# Rocketometer2148_MPU6050.net
KiCad netlist of a schematic drawn in EAGLE
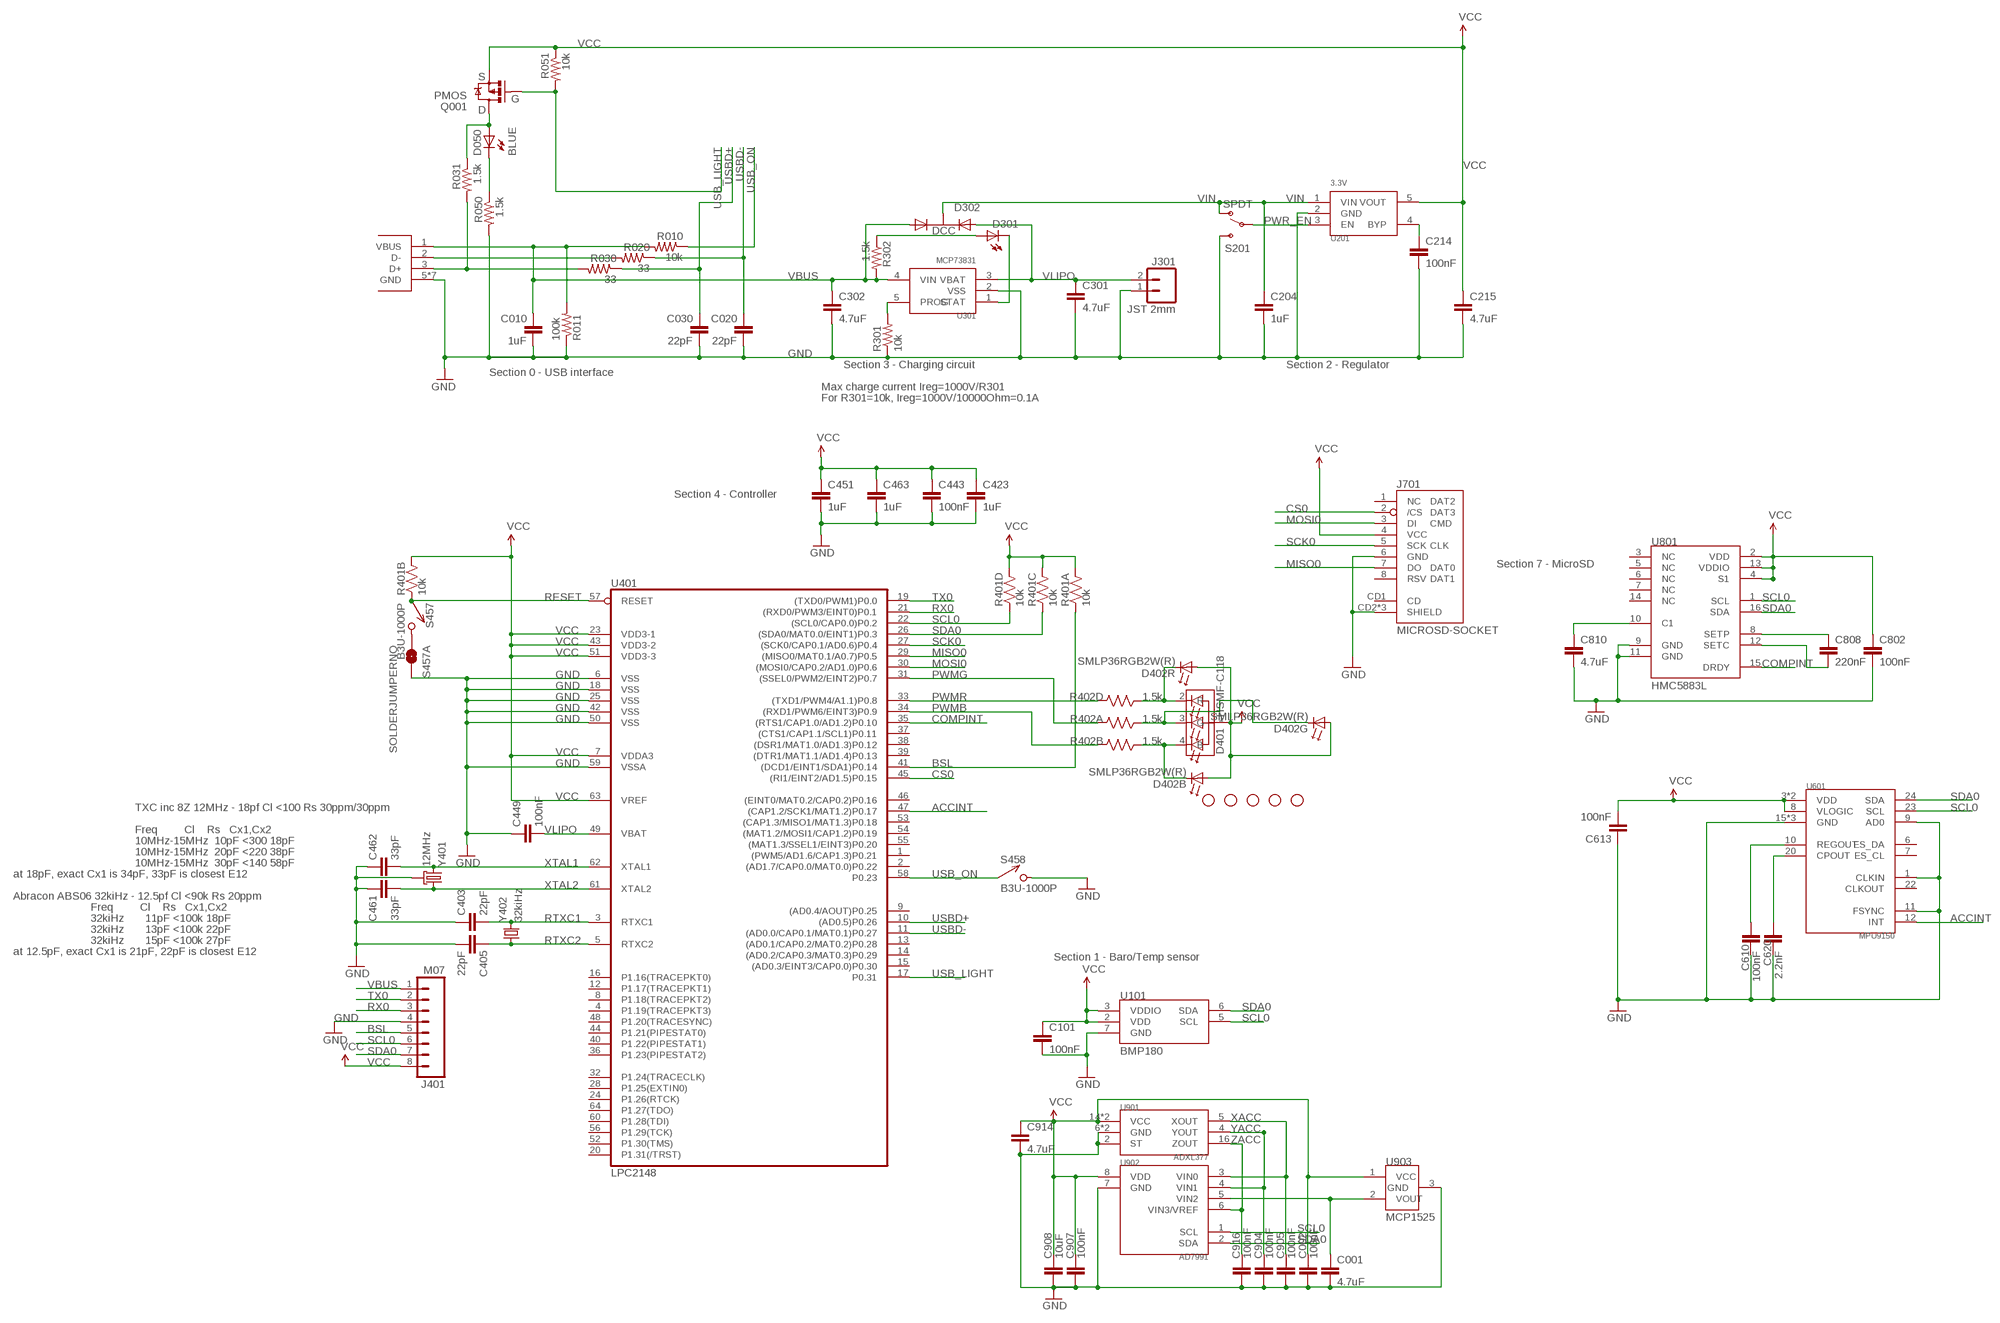
[diagram p0: schematic, sheet 1]

(export (version "E")
  (design (tool "Eeschema 10.0.6"))
  (components
    (comp (ref "C001")
      (value "4.7uF")
      (footprint "eagle-import:0402-CAP")
      (libsource (lib "eagle-import") (part "CAP0402-CAP"))
    )
    (comp (ref "C002")
      (value "100nF")
      (footprint "eagle-import:0402-CAP")
      (libsource (lib "eagle-import") (part "SparkFun-Passives_CAP0402-CAP"))
    )
    (comp (ref "C010")
      (value "1uF")
      (footprint "eagle-import:0402-CAP")
      (libsource (lib "eagle-import") (part "CAP0402-CAP"))
    )
    (comp (ref "C020")
      (value "22pF")
      (footprint "eagle-import:0402-CAP")
      (libsource (lib "eagle-import") (part "CAP0402-CAP"))
    )
    (comp (ref "C030")
      (value "22pF")
      (footprint "eagle-import:0402-CAP")
      (libsource (lib "eagle-import") (part "CAP0402-CAP"))
    )
    (comp (ref "C101")
      (value "100nF")
      (footprint "eagle-import:0402-CAP")
      (libsource (lib "eagle-import") (part "CAP0402-CAP"))
    )
    (comp (ref "C204")
      (value "1uF")
      (footprint "eagle-import:0402-CAP")
      (libsource (lib "eagle-import") (part "CAP0402-CAP"))
    )
    (comp (ref "C214")
      (value "100nF")
      (footprint "eagle-import:0402-CAP")
      (libsource (lib "eagle-import") (part "CAP0402-CAP"))
    )
    (comp (ref "C215")
      (value "4.7uF")
      (footprint "eagle-import:0402-CAP")
      (libsource (lib "eagle-import") (part "CAP0402-CAP"))
    )
    (comp (ref "C301")
      (value "4.7uF")
      (footprint "eagle-import:0402-CAP")
      (libsource (lib "eagle-import") (part "CAP0402-CAP"))
    )
    (comp (ref "C302")
      (value "4.7uF")
      (footprint "eagle-import:0402-CAP")
      (libsource (lib "eagle-import") (part "CAP0402-CAP"))
    )
    (comp (ref "C403")
      (value "22pF")
      (footprint "eagle-import:0402-CAP")
      (libsource (lib "eagle-import") (part "CAP0402-CAP"))
    )
    (comp (ref "C405")
      (value "22pF")
      (footprint "eagle-import:0402-CAP")
      (libsource (lib "eagle-import") (part "CAP0402-CAP"))
    )
    (comp (ref "C423")
      (value "1uF")
      (footprint "eagle-import:0402-CAP")
      (libsource (lib "eagle-import") (part "CAP0402-CAP"))
    )
    (comp (ref "C443")
      (value "100nF")
      (footprint "eagle-import:0402-CAP")
      (libsource (lib "eagle-import") (part "CAP0402-CAP"))
    )
    (comp (ref "C449")
      (value "100nF")
      (footprint "eagle-import:0402-CAP")
      (libsource (lib "eagle-import") (part "CAP0402-CAP"))
    )
    (comp (ref "C451")
      (value "1uF")
      (footprint "eagle-import:0402-CAP")
      (libsource (lib "eagle-import") (part "CAP0402-CAP"))
    )
    (comp (ref "C461")
      (value "33pF")
      (footprint "eagle-import:0402-CAP")
      (libsource (lib "eagle-import") (part "CAP0402-CAP"))
    )
    (comp (ref "C462")
      (value "33pF")
      (footprint "eagle-import:0402-CAP")
      (libsource (lib "eagle-import") (part "CAP0402-CAP"))
    )
    (comp (ref "C463")
      (value "1uF")
      (footprint "eagle-import:0402-CAP")
      (libsource (lib "eagle-import") (part "CAP0402-CAP"))
    )
    (comp (ref "C610")
      (value "100nF")
      (footprint "eagle-import:0402-CAP")
      (libsource (lib "eagle-import") (part "CAP0402-CAP"))
    )
    (comp (ref "C613")
      (value "100nF")
      (footprint "eagle-import:0402-CAP")
      (libsource (lib "eagle-import") (part "CAP0402-CAP"))
    )
    (comp (ref "C620")
      (value "2.2nF")
      (footprint "eagle-import:0402-CAP")
      (libsource (lib "eagle-import") (part "CAP0402-CAP"))
    )
    (comp (ref "C802")
      (value "100nF")
      (footprint "eagle-import:0402-CAP")
      (libsource (lib "eagle-import") (part "CAP0402-CAP"))
    )
    (comp (ref "C808")
      (value "220nF")
      (footprint "eagle-import:0402-CAP")
      (libsource (lib "eagle-import") (part "CAP0402-CAP"))
    )
    (comp (ref "C810")
      (value "4.7uF")
      (footprint "eagle-import:0402-CAP")
      (libsource (lib "eagle-import") (part "CAP0402-CAP"))
    )
    (comp (ref "C904")
      (value "100nF")
      (footprint "eagle-import:0402-CAP")
      (libsource (lib "eagle-import") (part "CAP0402-CAP"))
    )
    (comp (ref "C905")
      (value "100nF")
      (footprint "eagle-import:0402-CAP")
      (libsource (lib "eagle-import") (part "CAP0402-CAP"))
    )
    (comp (ref "C907")
      (value "100nF")
      (footprint "eagle-import:0402-CAP")
      (libsource (lib "eagle-import") (part "SparkFun-Passives_CAP0402-CAP"))
    )
    (comp (ref "C908")
      (value "10uF")
      (footprint "eagle-import:0603-CAP")
      (libsource (lib "eagle-import") (part "CAP0603-CAP"))
    )
    (comp (ref "C914")
      (value "4.7uF")
      (footprint "eagle-import:0402-CAP")
      (libsource (lib "eagle-import") (part "CAP0402-CAP"))
    )
    (comp (ref "C916")
      (value "100nF")
      (footprint "eagle-import:0402-CAP")
      (libsource (lib "eagle-import") (part "CAP0402-CAP"))
    )
    (comp (ref "D050")
      (value "BLUE")
      (footprint "eagle-import:LED-0603")
      (libsource (lib "eagle-import") (part "LED0603"))
    )
    (comp (ref "D301")
      (value "YELLOW")
      (footprint "eagle-import:LED-0603")
      (libsource (lib "eagle-import") (part "LED0603"))
    )
    (comp (ref "D302")
      (value "DCC")
      (footprint "eagle-import:SOT-23-3")
      (libsource (lib "eagle-import") (part "PMEG2005CT"))
    )
    (comp (ref "D401")
      (value "HSMF-C118")
      (footprint "eagle-import:HSMF-C118")
      (libsource (lib "eagle-import") (part "HSMF-C118"))
    )
    (comp (ref "D402")
      (value "SMLP36RGB2W(R)")
      (footprint "eagle-import:SMLP36")
      (libsource (lib "eagle-import") (part "SMLP36RGB2W(R)"))
    )
    (comp (ref "J001")
      (value "USB_MICROB_JST")
      (footprint "eagle-import:UB-MC5BR3-SD204-4S")
      (libsource (lib "eagle-import") (part "USB_MICROB_JST"))
    )
    (comp (ref "J301")
      (value "JST 2mm")
      (footprint "eagle-import:JST-2-SMD")
      (libsource (lib "eagle-import") (part "M02-JST-2MM-SMT"))
    )
    (comp (ref "J401")
      (value "M07")
      (footprint "eagle-import:1X08")
      (libsource (lib "eagle-import") (part "M081X08"))
    )
    (comp (ref "J701")
      (value "MICROSD-SOCKET")
      (footprint "eagle-import:MICROSD-SOCKET-PP")
      (libsource (lib "eagle-import") (part "MICROSD-SOCKET"))
    )
    (comp (ref "JP1")
      (value "STAND-OFFTIGHT")
      (footprint "eagle-import:STAND-OFF-TIGHT")
      (libsource (lib "eagle-import") (part "STAND-OFFTIGHT"))
    )
    (comp (ref "JP2")
      (value "STAND-OFFTIGHT")
      (footprint "eagle-import:STAND-OFF-TIGHT")
      (libsource (lib "eagle-import") (part "STAND-OFFTIGHT"))
    )
    (comp (ref "JP3")
      (value "STAND-OFFTIGHT")
      (footprint "eagle-import:STAND-OFF-TIGHT")
      (libsource (lib "eagle-import") (part "STAND-OFFTIGHT"))
    )
    (comp (ref "JP4")
      (value "STAND-OFFTIGHT")
      (footprint "eagle-import:STAND-OFF-TIGHT")
      (libsource (lib "eagle-import") (part "STAND-OFFTIGHT"))
    )
    (comp (ref "JP5")
      (value "STAND-OFFTIGHT")
      (footprint "eagle-import:STAND-OFF-TIGHT")
      (libsource (lib "eagle-import") (part "STAND-OFFTIGHT"))
    )
    (comp (ref "Q001")
      (value "PMOS")
      (footprint "eagle-import:SOT23-3")
      (libsource (lib "eagle-import") (part "MOSFET-PCHANNELSMD"))
    )
    (comp (ref "R010")
      (value "10k")
      (footprint "eagle-import:0402-RES")
      (libsource (lib "eagle-import") (part "RESISTOR0402-RES"))
    )
    (comp (ref "R011")
      (value "100k")
      (footprint "eagle-import:0402-RES")
      (libsource (lib "eagle-import") (part "RESISTOR0402-RES"))
    )
    (comp (ref "R020")
      (value "33")
      (footprint "eagle-import:0402-RES")
      (libsource (lib "eagle-import") (part "RESISTOR0402-RES"))
    )
    (comp (ref "R030")
      (value "33")
      (footprint "eagle-import:0402-RES")
      (libsource (lib "eagle-import") (part "RESISTOR0402-RES"))
    )
    (comp (ref "R031")
      (value "1.5k")
      (footprint "eagle-import:0402-RES")
      (libsource (lib "eagle-import") (part "RESISTOR0402-RES"))
    )
    (comp (ref "R050")
      (value "1.5k")
      (footprint "eagle-import:0402-RES")
      (libsource (lib "eagle-import") (part "RESISTOR0402-RES"))
    )
    (comp (ref "R051")
      (value "10k")
      (footprint "eagle-import:0402-RES")
      (libsource (lib "eagle-import") (part "RESISTOR0402-RES"))
    )
    (comp (ref "R301")
      (value "10k")
      (footprint "eagle-import:0402-RES")
      (libsource (lib "eagle-import") (part "RESISTOR0402-RES"))
    )
    (comp (ref "R302")
      (value "1.5k")
      (footprint "eagle-import:0402-RES")
      (libsource (lib "eagle-import") (part "RESISTOR0402-RES"))
    )
    (comp (ref "R401")
      (value "10k")
      (footprint "eagle-import:CRA04")
      (fields (field (name "DIGIKEY") "CRA4S810KCT-ND"))
      (libsource (lib "eagle-import") (part "RP404"))
    )
    (comp (ref "R402")
      (value "1.5k")
      (footprint "eagle-import:CRA04")
      (fields (field (name "DIGIKEY") "CRA4S81.5KCT-ND"))
      (libsource (lib "eagle-import") (part "RP404"))
    )
    (comp (ref "S201")
      (value "SPDT")
      (footprint "eagle-import:AYZ0202")
      (libsource (lib "eagle-import") (part "SWITCH-SPSTSMD"))
    )
    (comp (ref "S457")
      (value "B3U-1000P")
      (footprint "eagle-import:B3U-1000P")
      (libsource (lib "eagle-import") (part "B3U-1000P"))
    )
    (comp (ref "S457A")
      (value "SOLDERJUMPERNO")
      (footprint "eagle-import:SJ_2S-NO")
      (libsource (lib "eagle-import") (part "SOLDERJUMPERNO"))
    )
    (comp (ref "S458")
      (value "B3U-1000P")
      (footprint "eagle-import:B3U-1000P")
      (libsource (lib "eagle-import") (part "B3U-1000P"))
    )
    (comp (ref "U101")
      (value "BMP180")
      (footprint "eagle-import:BMP180")
      (libsource (lib "eagle-import") (part "BMP180"))
    )
    (comp (ref "U201")
      (value "3.3V")
      (footprint "eagle-import:SOT-23-5")
      (libsource (lib "eagle-import") (part "MIC5319D5"))
    )
    (comp (ref "U301")
      (value "MCP73831")
      (footprint "eagle-import:SOT-23-5")
      (libsource (lib "eagle-import") (part "MCP73831"))
    )
    (comp (ref "U401")
      (value "LPC2148")
      (footprint "eagle-import:SQFP-S-10X10-64")
      (libsource (lib "eagle-import") (part "LPC213X"))
    )
    (comp (ref "U601")
      (value "MPU9150")
      (footprint "eagle-import:LLGA24")
      (libsource (lib "eagle-import") (part "MPU9150"))
    )
    (comp (ref "U801")
      (value "HMC5883L")
      (footprint "eagle-import:16LPCC")
      (libsource (lib "eagle-import") (part "HMC5883LSMD"))
    )
    (comp (ref "U901")
      (value "ADXL377")
      (footprint "eagle-import:ADXL377")
      (libsource (lib "eagle-import") (part "ADXL377"))
    )
    (comp (ref "U902")
      (value "AD7991")
      (footprint "eagle-import:SOT-23-8")
      (libsource (lib "eagle-import") (part "AD799X"))
    )
    (comp (ref "U903")
      (value "MCP1525")
      (footprint "eagle-import:SOT-23-3")
      (libsource (lib "eagle-import") (part "MCP1525"))
    )
    (comp (ref "Y401")
      (value "12MHz")
      (footprint "eagle-import:CRYSTAL_SMD_2MM_2_5MM")
      (libsource (lib "eagle-import") (part "CX2520"))
    )
    (comp (ref "Y402")
      (value "32kiHz")
      (footprint "eagle-import:ABS06")
      (libsource (lib "eagle-import") (part "ABS06"))
    )
  )
  (nets
    (net (code "1") (name "/ACCINT") (class "Default")
      (node (ref "U401") (pin "47") (pinfunction "(CAP1.2/SCK1/MAT1.2)P0.17_47") (pintype "bidirectional"))
      (node (ref "U601") (pin "12") (pinfunction "INT_12") (pintype "bidirectional"))
    )
    (net (code "2") (name "/BSL") (class "Default")
      (node (ref "J401") (pin "5") (pinfunction "5_5") (pintype "passive"))
      (node (ref "R401") (pin "1") (pinfunction "1_1") (pintype "passive"))
      (node (ref "U401") (pin "41") (pinfunction "(DCD1/EINT1/SDA1)P0.14_41") (pintype "bidirectional"))
    )
    (net (code "3") (name "/COMPINT") (class "Default")
      (node (ref "U401") (pin "35") (pinfunction "(RTS1/CAP1.0/AD1.2)P0.10_35") (pintype "bidirectional"))
      (node (ref "U801") (pin "15") (pinfunction "DRDY_15") (pintype "bidirectional"))
    )
    (net (code "4") (name "/CS0") (class "Default")
      (node (ref "J701") (pin "2") (pinfunction "/CS_2") (pintype "bidirectional"))
      (node (ref "U401") (pin "45") (pinfunction "(RI1/EINT2/AD1.5)P0.15_45") (pintype "bidirectional"))
    )
    (net (code "5") (name "/MISO0") (class "Default")
      (node (ref "J701") (pin "7") (pinfunction "DO_7") (pintype "bidirectional"))
      (node (ref "U401") (pin "29") (pinfunction "(MISO0/MAT0.1/A0.7)P0.5_29") (pintype "bidirectional"))
    )
    (net (code "6") (name "/MOSI0") (class "Default")
      (node (ref "J701") (pin "3") (pinfunction "DI_3") (pintype "bidirectional"))
      (node (ref "U401") (pin "30") (pinfunction "(MOSI0/CAP0.2/AD1.0)P0.6_30") (pintype "bidirectional"))
    )
    (net (code "7") (name "/PWMB") (class "Default")
      (node (ref "R402") (pin "7") (pinfunction "2_7") (pintype "passive"))
      (node (ref "U401") (pin "34") (pinfunction "(RXD1/PWM6/EINT3)P0.9_34") (pintype "bidirectional"))
    )
    (net (code "8") (name "/PWMG") (class "Default")
      (node (ref "R402") (pin "8") (pinfunction "2_8") (pintype "passive"))
      (node (ref "U401") (pin "31") (pinfunction "(SSEL0/PWM2/EINT2)P0.7_31") (pintype "bidirectional"))
    )
    (net (code "9") (name "/PWMR") (class "Default")
      (node (ref "R402") (pin "5") (pinfunction "2_5") (pintype "passive"))
      (node (ref "U401") (pin "33") (pinfunction "(TXD1/PWM4/A1.1)P0.8_33") (pintype "bidirectional"))
    )
    (net (code "10") (name "/PWR_EN") (class "Default")
      (node (ref "S201") (pin "2") (pinfunction "P_2") (pintype "passive"))
      (node (ref "U201") (pin "3") (pinfunction "EN_3") (pintype "bidirectional"))
    )
    (net (code "11") (name "/RESET") (class "Default")
      (node (ref "R401") (pin "2") (pinfunction "1_2") (pintype "passive"))
      (node (ref "S457") (pin "P$1") (pinfunction "1_P$1") (pintype "bidirectional"))
      (node (ref "U401") (pin "57") (pinfunction "RESET_57") (pintype "input"))
    )
    (net (code "12") (name "/RTXC1") (class "Default")
      (node (ref "C403") (pin "2") (pinfunction "2_2") (pintype "passive"))
      (node (ref "U401") (pin "3") (pinfunction "RTXC1_3") (pintype "input"))
      (node (ref "Y402") (pin "2") (pinfunction "2_2") (pintype "passive"))
    )
    (net (code "13") (name "/RTXC2") (class "Default")
      (node (ref "C405") (pin "1") (pinfunction "1_1") (pintype "passive"))
      (node (ref "U401") (pin "5") (pinfunction "RTXC2_5") (pintype "output"))
      (node (ref "Y402") (pin "1") (pinfunction "1_1") (pintype "passive"))
    )
    (net (code "14") (name "/RX0") (class "Default")
      (node (ref "J401") (pin "3") (pinfunction "3_3") (pintype "passive"))
      (node (ref "U401") (pin "21") (pinfunction "(RXD0/PWM3/EINT0)P0.1_21") (pintype "bidirectional"))
    )
    (net (code "15") (name "/SCK0") (class "Default")
      (node (ref "J701") (pin "5") (pinfunction "SCK_5") (pintype "bidirectional"))
      (node (ref "U401") (pin "27") (pinfunction "(SCK0/CAP0.1/AD0.6)P0.4_27") (pintype "bidirectional"))
    )
    (net (code "16") (name "/SCL0") (class "Default")
      (node (ref "J401") (pin "6") (pinfunction "6_6") (pintype "passive"))
      (node (ref "R401") (pin "4") (pinfunction "1_4") (pintype "passive"))
      (node (ref "U101") (pin "5") (pinfunction "SCL_5") (pintype "input"))
      (node (ref "U401") (pin "22") (pinfunction "(SCL0/CAP0.0)P0.2_22") (pintype "bidirectional"))
      (node (ref "U601") (pin "23") (pinfunction "SCL_23") (pintype "bidirectional"))
      (node (ref "U801") (pin "1") (pinfunction "SCL_1") (pintype "bidirectional"))
      (node (ref "U902") (pin "1") (pinfunction "SCL_1") (pintype "bidirectional"))
    )
    (net (code "17") (name "/SDA0") (class "Default")
      (node (ref "J401") (pin "7") (pinfunction "7_7") (pintype "passive"))
      (node (ref "R401") (pin "3") (pinfunction "1_3") (pintype "passive"))
      (node (ref "U101") (pin "6") (pinfunction "SDA_6") (pintype "bidirectional"))
      (node (ref "U401") (pin "26") (pinfunction "(SDA0/MAT0.0/EINT1)P0.3_26") (pintype "bidirectional"))
      (node (ref "U601") (pin "24") (pinfunction "SDA_24") (pintype "bidirectional"))
      (node (ref "U801") (pin "16") (pinfunction "SDA_16") (pintype "bidirectional"))
      (node (ref "U902") (pin "2") (pinfunction "SDA_2") (pintype "bidirectional"))
    )
    (net (code "18") (name "/TX0") (class "Default")
      (node (ref "J401") (pin "2") (pinfunction "2_2") (pintype "passive"))
      (node (ref "U401") (pin "19") (pinfunction "(TXD0/PWM1)P0.0_19") (pintype "bidirectional"))
    )
    (net (code "19") (name "/USBD+") (class "Default")
      (node (ref "C030") (pin "1") (pinfunction "1_1") (pintype "passive"))
      (node (ref "R030") (pin "1") (pinfunction "1_1") (pintype "passive"))
      (node (ref "U401") (pin "10") (pinfunction "(AD0.5)P0.26_10") (pintype "bidirectional"))
    )
    (net (code "20") (name "/USBD-") (class "Default")
      (node (ref "C020") (pin "1") (pinfunction "1_1") (pintype "passive"))
      (node (ref "R020") (pin "1") (pinfunction "1_1") (pintype "passive"))
      (node (ref "U401") (pin "11") (pinfunction "(AD0.0/CAP0.1/MAT0.1)P0.27_11") (pintype "bidirectional"))
    )
    (net (code "21") (name "/USB_LIGHT") (class "Default")
      (node (ref "Q001") (pin "1") (pinfunction "G_1") (pintype "passive"))
      (node (ref "R051") (pin "2") (pinfunction "2_2") (pintype "passive"))
      (node (ref "U401") (pin "17") (pinfunction "P0.31_17") (pintype "output"))
    )
    (net (code "22") (name "/USB_ON") (class "Default")
      (node (ref "R010") (pin "1") (pinfunction "1_1") (pintype "passive"))
      (node (ref "S458") (pin "P$1") (pinfunction "1_P$1") (pintype "bidirectional"))
      (node (ref "U401") (pin "58") (pinfunction "P0.23_58") (pintype "bidirectional"))
    )
    (net (code "23") (name "/VBUS") (class "Default")
      (node (ref "C010") (pin "1") (pinfunction "1_1") (pintype "passive"))
      (node (ref "C302") (pin "1") (pinfunction "1_1") (pintype "passive"))
      (node (ref "D302") (pin "1") (pinfunction "A1_1") (pintype "passive"))
      (node (ref "J001") (pin "1") (pinfunction "VBUS_1") (pintype "bidirectional"))
      (node (ref "J401") (pin "1") (pinfunction "1_1") (pintype "passive"))
      (node (ref "R010") (pin "2") (pinfunction "2_2") (pintype "passive"))
      (node (ref "R011") (pin "2") (pinfunction "2_2") (pintype "passive"))
      (node (ref "R302") (pin "2") (pinfunction "2_2") (pintype "passive"))
      (node (ref "U301") (pin "4") (pinfunction "VIN_4") (pintype "power_in"))
    )
    (net (code "24") (name "/VIN") (class "Default")
      (node (ref "C204") (pin "1") (pinfunction "1_1") (pintype "passive"))
      (node (ref "D302") (pin "3") (pinfunction "K_3") (pintype "passive"))
      (node (ref "S201") (pin "1") (pinfunction "O_1") (pintype "passive"))
      (node (ref "U201") (pin "1") (pinfunction "VIN_1") (pintype "bidirectional"))
    )
    (net (code "25") (name "/VLIPO") (class "Default")
      (node (ref "C301") (pin "1") (pinfunction "1_1") (pintype "passive"))
      (node (ref "C449") (pin "2") (pinfunction "2_2") (pintype "passive"))
      (node (ref "D302") (pin "2") (pinfunction "A2_2") (pintype "passive"))
      (node (ref "J301") (pin "2") (pinfunction "2_2") (pintype "passive"))
      (node (ref "U301") (pin "3") (pinfunction "VBAT_3") (pintype "power_in"))
      (node (ref "U401") (pin "49") (pinfunction "VBAT_49") (pintype "power_in"))
    )
    (net (code "26") (name "/XACC") (class "Default")
      (node (ref "C905") (pin "1") (pinfunction "1_1") (pintype "passive"))
      (node (ref "U901") (pin "5") (pinfunction "XOUT_5") (pintype "bidirectional"))
      (node (ref "U902") (pin "3") (pinfunction "VIN0_3") (pintype "bidirectional"))
    )
    (net (code "27") (name "/XTAL1") (class "Default")
      (node (ref "C462") (pin "2") (pinfunction "2_2") (pintype "passive"))
      (node (ref "U401") (pin "62") (pinfunction "XTAL1_62") (pintype "input"))
      (node (ref "Y401") (pin "3") (pinfunction "2_3") (pintype "passive"))
    )
    (net (code "28") (name "/XTAL2") (class "Default")
      (node (ref "C461") (pin "2") (pinfunction "2_2") (pintype "passive"))
      (node (ref "U401") (pin "61") (pinfunction "XTAL2_61") (pintype "output"))
      (node (ref "Y401") (pin "1") (pinfunction "1_1") (pintype "passive"))
    )
    (net (code "29") (name "/YACC") (class "Default")
      (node (ref "C904") (pin "1") (pinfunction "1_1") (pintype "passive"))
      (node (ref "U901") (pin "4") (pinfunction "YOUT_4") (pintype "bidirectional"))
      (node (ref "U902") (pin "4") (pinfunction "VIN1_4") (pintype "bidirectional"))
    )
    (net (code "30") (name "/ZACC") (class "Default")
      (node (ref "C916") (pin "1") (pinfunction "1_1") (pintype "passive"))
      (node (ref "U901") (pin "16") (pinfunction "ZOUT_16") (pintype "bidirectional"))
      (node (ref "U902") (pin "6") (pinfunction "VIN3/VREF_6") (pintype "bidirectional"))
    )
    (net (code "31") (name "GND") (class "Default")
      (node (ref "C001") (pin "2") (pinfunction "2_2") (pintype "passive"))
      (node (ref "C002") (pin "2") (pinfunction "2_2") (pintype "passive"))
      (node (ref "C010") (pin "2") (pinfunction "2_2") (pintype "passive"))
      (node (ref "C020") (pin "2") (pinfunction "2_2") (pintype "passive"))
      (node (ref "C030") (pin "2") (pinfunction "2_2") (pintype "passive"))
      (node (ref "C101") (pin "2") (pinfunction "2_2") (pintype "passive"))
      (node (ref "C204") (pin "2") (pinfunction "2_2") (pintype "passive"))
      (node (ref "C214") (pin "2") (pinfunction "2_2") (pintype "passive"))
      (node (ref "C215") (pin "2") (pinfunction "2_2") (pintype "passive"))
      (node (ref "C301") (pin "2") (pinfunction "2_2") (pintype "passive"))
      (node (ref "C302") (pin "2") (pinfunction "2_2") (pintype "passive"))
      (node (ref "C403") (pin "1") (pinfunction "1_1") (pintype "passive"))
      (node (ref "C405") (pin "2") (pinfunction "2_2") (pintype "passive"))
      (node (ref "C423") (pin "2") (pinfunction "2_2") (pintype "passive"))
      (node (ref "C443") (pin "2") (pinfunction "2_2") (pintype "passive"))
      (node (ref "C449") (pin "1") (pinfunction "1_1") (pintype "passive"))
      (node (ref "C451") (pin "2") (pinfunction "2_2") (pintype "passive"))
      (node (ref "C461") (pin "1") (pinfunction "1_1") (pintype "passive"))
      (node (ref "C462") (pin "1") (pinfunction "1_1") (pintype "passive"))
      (node (ref "C463") (pin "2") (pinfunction "2_2") (pintype "passive"))
      (node (ref "C610") (pin "2") (pinfunction "2_2") (pintype "passive"))
      (node (ref "C613") (pin "1") (pinfunction "1_1") (pintype "passive"))
      (node (ref "C620") (pin "1") (pinfunction "1_1") (pintype "passive"))
      (node (ref "C802") (pin "2") (pinfunction "2_2") (pintype "passive"))
      (node (ref "C810") (pin "2") (pinfunction "2_2") (pintype "passive"))
      (node (ref "C904") (pin "2") (pinfunction "2_2") (pintype "passive"))
      (node (ref "C905") (pin "2") (pinfunction "2_2") (pintype "passive"))
      (node (ref "C907") (pin "2") (pinfunction "2_2") (pintype "passive"))
      (node (ref "C908") (pin "2") (pinfunction "2_2") (pintype "passive"))
      (node (ref "C914") (pin "2") (pinfunction "2_2") (pintype "passive"))
      (node (ref "C916") (pin "2") (pinfunction "2_2") (pintype "passive"))
      (node (ref "J001") (pin "5") (pinfunction "GND_5") (pintype "bidirectional"))
      (node (ref "J001") (pin "P$10") (pinfunction "GND_P$10") (pintype "bidirectional"))
      (node (ref "J001") (pin "P$11") (pinfunction "GND_P$11") (pintype "bidirectional"))
      (node (ref "J001") (pin "P$6") (pinfunction "GND_P$6") (pintype "bidirectional"))
      (node (ref "J001") (pin "P$7") (pinfunction "GND_P$7") (pintype "bidirectional"))
      (node (ref "J001") (pin "P$8") (pinfunction "GND_P$8") (pintype "bidirectional"))
      (node (ref "J001") (pin "P$9") (pinfunction "GND_P$9") (pintype "bidirectional"))
      (node (ref "J301") (pin "1") (pinfunction "1_1") (pintype "passive"))
      (node (ref "J401") (pin "4") (pinfunction "4_4") (pintype "passive"))
      (node (ref "J701") (pin "6") (pinfunction "GND_6") (pintype "bidirectional"))
      (node (ref "J701") (pin "CD2") (pinfunction "SHIELD_CD2") (pintype "bidirectional"))
      (node (ref "J701") (pin "GND1") (pinfunction "SHIELD_GND1") (pintype "bidirectional"))
      (node (ref "J701") (pin "GND3") (pinfunction "SHIELD_GND3") (pintype "bidirectional"))
      (node (ref "R011") (pin "1") (pinfunction "1_1") (pintype "passive"))
      (node (ref "R050") (pin "2") (pinfunction "2_2") (pintype "passive"))
      (node (ref "R301") (pin "1") (pinfunction "1_1") (pintype "passive"))
      (node (ref "S201") (pin "3") (pinfunction "S_3") (pintype "passive"))
      (node (ref "S457A") (pin "2") (pinfunction "2_2") (pintype "passive"))
      (node (ref "S458") (pin "P$2") (pinfunction "2_P$2") (pintype "bidirectional"))
      (node (ref "U101") (pin "7") (pinfunction "GND_7") (pintype "power_in"))
      (node (ref "U201") (pin "2") (pinfunction "GND_2") (pintype "bidirectional"))
      (node (ref "U301") (pin "2") (pinfunction "VSS_2") (pintype "power_in"))
      (node (ref "U401") (pin "18") (pinfunction "VSS_18") (pintype "power_in"))
      (node (ref "U401") (pin "25") (pinfunction "VSS_25") (pintype "power_in"))
      (node (ref "U401") (pin "42") (pinfunction "VSS_42") (pintype "power_in"))
      (node (ref "U401") (pin "50") (pinfunction "VSS_50") (pintype "power_in"))
      (node (ref "U401") (pin "59") (pinfunction "VSSA_59") (pintype "power_in"))
      (node (ref "U401") (pin "6") (pinfunction "VSS_6") (pintype "power_in"))
      (node (ref "U601") (pin "1") (pinfunction "CLKIN_1") (pintype "bidirectional"))
      (node (ref "U601") (pin "11") (pinfunction "FSYNC_11") (pintype "bidirectional"))
      (node (ref "U601") (pin "15") (pinfunction "GND_15") (pintype "bidirectional"))
      (node (ref "U601") (pin "17") (pinfunction "GND_17") (pintype "bidirectional"))
      (node (ref "U601") (pin "18") (pinfunction "GND_18") (pintype "bidirectional"))
      (node (ref "U601") (pin "9") (pinfunction "AD0_9") (pintype "bidirectional"))
      (node (ref "U801") (pin "11") (pinfunction "GND_11") (pintype "bidirectional"))
      (node (ref "U801") (pin "9") (pinfunction "GND_9") (pintype "bidirectional"))
      (node (ref "U901") (pin "2") (pinfunction "ST_2") (pintype "bidirectional"))
      (node (ref "U901") (pin "6") (pinfunction "GND_6") (pintype "bidirectional"))
      (node (ref "U901") (pin "7") (pinfunction "GND_7") (pintype "bidirectional"))
      (node (ref "U902") (pin "7") (pinfunction "GND_7") (pintype "bidirectional"))
      (node (ref "U903") (pin "3") (pinfunction "GND_3") (pintype "bidirectional"))
      (node (ref "Y401") (pin "2") (pinfunction "GND_2") (pintype "passive"))
      (node (ref "Y401") (pin "4") (pinfunction "GND_4") (pintype "passive"))
    )
    (net (code "32") (name "Net-(D050-PadC)") (class "Default")
      (node (ref "D050") (pin "C") (pinfunction "C_C") (pintype "passive"))
      (node (ref "R050") (pin "1") (pinfunction "1_1") (pintype "passive"))
    )
    (net (code "33") (name "Net-(D301-PadA)") (class "Default")
      (node (ref "D301") (pin "A") (pinfunction "A_A") (pintype "passive"))
      (node (ref "R302") (pin "1") (pinfunction "1_1") (pintype "passive"))
    )
    (net (code "34") (name "Net-(D401-B)") (class "Default")
      (node (ref "D401") (pin "4") (pinfunction "B_4") (pintype "passive"))
      (node (ref "D402") (pin "1") (pinfunction "C_1") (pintype "passive"))
      (node (ref "R402") (pin "2") (pinfunction "1_2") (pintype "passive"))
    )
    (net (code "35") (name "Net-(D401-G)") (class "Default")
      (node (ref "D401") (pin "3") (pinfunction "G_3") (pintype "passive"))
      (node (ref "D402") (pin "5") (pinfunction "C_5") (pintype "passive"))
      (node (ref "R402") (pin "1") (pinfunction "1_1") (pintype "passive"))
    )
    (net (code "36") (name "Net-(D401-R)") (class "Default")
      (node (ref "D401") (pin "2") (pinfunction "R_2") (pintype "passive"))
      (node (ref "D402") (pin "3") (pinfunction "C_3") (pintype "passive"))
      (node (ref "R402") (pin "4") (pinfunction "1_4") (pintype "passive"))
    )
    (net (code "37") (name "Net-(J001-D+)") (class "Default")
      (node (ref "J001") (pin "3") (pinfunction "D+_3") (pintype "bidirectional"))
      (node (ref "R030") (pin "2") (pinfunction "2_2") (pintype "passive"))
      (node (ref "R031") (pin "2") (pinfunction "2_2") (pintype "passive"))
    )
    (net (code "38") (name "Net-(J001-D-)") (class "Default")
      (node (ref "J001") (pin "2") (pinfunction "D-_2") (pintype "bidirectional"))
      (node (ref "R020") (pin "2") (pinfunction "2_2") (pintype "passive"))
    )
    (net (code "39") (name "Net-(Q001-D)") (class "Default")
      (node (ref "D050") (pin "A") (pinfunction "A_A") (pintype "passive"))
      (node (ref "Q001") (pin "3") (pinfunction "D_3") (pintype "passive"))
      (node (ref "R031") (pin "1") (pinfunction "1_1") (pintype "passive"))
    )
    (net (code "40") (name "Net-(S457-2)") (class "Default")
      (node (ref "S457") (pin "P$2") (pinfunction "2_P$2") (pintype "bidirectional"))
      (node (ref "S457A") (pin "1") (pinfunction "1_1") (pintype "passive"))
    )
    (net (code "41") (name "Net-(U201-BYP)") (class "Default")
      (node (ref "C214") (pin "1") (pinfunction "1_1") (pintype "passive"))
      (node (ref "U201") (pin "4") (pinfunction "BYP_4") (pintype "bidirectional"))
    )
    (net (code "42") (name "Net-(U301-PROG)") (class "Default")
      (node (ref "R301") (pin "2") (pinfunction "2_2") (pintype "passive"))
      (node (ref "U301") (pin "5") (pinfunction "PROG_5") (pintype "passive"))
    )
    (net (code "43") (name "Net-(U301-STAT)") (class "Default")
      (node (ref "D301") (pin "C") (pinfunction "C_C") (pintype "passive"))
      (node (ref "U301") (pin "1") (pinfunction "STAT_1") (pintype "bidirectional"))
    )
    (net (code "44") (name "Net-(U601-CPOUT)") (class "Default")
      (node (ref "C620") (pin "2") (pinfunction "2_2") (pintype "passive"))
      (node (ref "U601") (pin "20") (pinfunction "CPOUT_20") (pintype "bidirectional"))
    )
    (net (code "45") (name "Net-(U601-REGOUT)") (class "Default")
      (node (ref "C610") (pin "1") (pinfunction "1_1") (pintype "passive"))
      (node (ref "U601") (pin "10") (pinfunction "REGOUT_10") (pintype "bidirectional"))
    )
    (net (code "46") (name "Net-(U801-C1)") (class "Default")
      (node (ref "C810") (pin "1") (pinfunction "1_1") (pintype "passive"))
      (node (ref "U801") (pin "10") (pinfunction "C1_10") (pintype "bidirectional"))
    )
    (net (code "47") (name "Net-(U801-SETC)") (class "Default")
      (node (ref "C808") (pin "2") (pinfunction "2_2") (pintype "passive"))
      (node (ref "U801") (pin "12") (pinfunction "SETC_12") (pintype "bidirectional"))
    )
    (net (code "48") (name "Net-(U801-SETP)") (class "Default")
      (node (ref "C808") (pin "1") (pinfunction "1_1") (pintype "passive"))
      (node (ref "U801") (pin "8") (pinfunction "SETP_8") (pintype "bidirectional"))
    )
    (net (code "49") (name "Net-(U902-VIN2)") (class "Default")
      (node (ref "C001") (pin "1") (pinfunction "1_1") (pintype "passive"))
      (node (ref "U902") (pin "5") (pinfunction "VIN2_5") (pintype "bidirectional"))
      (node (ref "U903") (pin "2") (pinfunction "VOUT_2") (pintype "bidirectional"))
    )
    (net (code "50") (name "VCC") (class "Default")
      (node (ref "C002") (pin "1") (pinfunction "1_1") (pintype "passive"))
      (node (ref "C101") (pin "1") (pinfunction "1_1") (pintype "passive"))
      (node (ref "C215") (pin "1") (pinfunction "1_1") (pintype "passive"))
      (node (ref "C423") (pin "1") (pinfunction "1_1") (pintype "passive"))
      (node (ref "C443") (pin "1") (pinfunction "1_1") (pintype "passive"))
      (node (ref "C451") (pin "1") (pinfunction "1_1") (pintype "passive"))
      (node (ref "C463") (pin "1") (pinfunction "1_1") (pintype "passive"))
      (node (ref "C613") (pin "2") (pinfunction "2_2") (pintype "passive"))
      (node (ref "C802") (pin "1") (pinfunction "1_1") (pintype "passive"))
      (node (ref "C907") (pin "1") (pinfunction "1_1") (pintype "passive"))
      (node (ref "C908") (pin "1") (pinfunction "1_1") (pintype "passive"))
      (node (ref "C914") (pin "1") (pinfunction "1_1") (pintype "passive"))
      (node (ref "D401") (pin "1") (pinfunction "A_1") (pintype "passive"))
      (node (ref "D402") (pin "2") (pinfunction "A_2") (pintype "passive"))
      (node (ref "D402") (pin "4") (pinfunction "A_4") (pintype "passive"))
      (node (ref "D402") (pin "6") (pinfunction "A_6") (pintype "passive"))
      (node (ref "J401") (pin "8") (pinfunction "8_8") (pintype "passive"))
      (node (ref "J701") (pin "4") (pinfunction "VCC_4") (pintype "bidirectional"))
      (node (ref "Q001") (pin "2") (pinfunction "S_2") (pintype "passive"))
      (node (ref "R051") (pin "1") (pinfunction "1_1") (pintype "passive"))
      (node (ref "R401") (pin "5") (pinfunction "2_5") (pintype "passive"))
      (node (ref "R401") (pin "6") (pinfunction "2_6") (pintype "passive"))
      (node (ref "R401") (pin "7") (pinfunction "2_7") (pintype "passive"))
      (node (ref "R401") (pin "8") (pinfunction "2_8") (pintype "passive"))
      (node (ref "U101") (pin "2") (pinfunction "VDD_2") (pintype "power_in"))
      (node (ref "U101") (pin "3") (pinfunction "VDDIO_3") (pintype "power_in"))
      (node (ref "U201") (pin "5") (pinfunction "VOUT_5") (pintype "bidirectional"))
      (node (ref "U401") (pin "23") (pinfunction "VDD3-1_23") (pintype "power_in"))
      (node (ref "U401") (pin "43") (pinfunction "VDD3-2_43") (pintype "power_in"))
      (node (ref "U401") (pin "51") (pinfunction "VDD3-3_51") (pintype "power_in"))
      (node (ref "U401") (pin "63") (pinfunction "VREF_63") (pintype "input"))
      (node (ref "U401") (pin "7") (pinfunction "VDDA3_7") (pintype "power_in"))
      (node (ref "U601") (pin "13") (pinfunction "VDD_13") (pintype "bidirectional"))
      (node (ref "U601") (pin "3") (pinfunction "VDD_3") (pintype "bidirectional"))
      (node (ref "U601") (pin "8") (pinfunction "VLOGIC_8") (pintype "bidirectional"))
      (node (ref "U801") (pin "13") (pinfunction "VDDIO_13") (pintype "bidirectional"))
      (node (ref "U801") (pin "2") (pinfunction "VDD_2") (pintype "bidirectional"))
      (node (ref "U801") (pin "4") (pinfunction "S1_4") (pintype "bidirectional"))
      (node (ref "U901") (pin "14") (pinfunction "VCC_14") (pintype "bidirectional"))
      (node (ref "U901") (pin "15") (pinfunction "VCC_15") (pintype "bidirectional"))
      (node (ref "U902") (pin "8") (pinfunction "VDD_8") (pintype "bidirectional"))
      (node (ref "U903") (pin "1") (pinfunction "VCC_1") (pintype "bidirectional"))
    )
    (net (code "51") (name "unconnected-(J701-CD-PadCD1)") (class "Default")
      (node (ref "J701") (pin "CD1") (pinfunction "CD_CD1") (pintype "bidirectional"))
    )
    (net (code "52") (name "unconnected-(J701-NC-Pad1)") (class "Default")
      (node (ref "J701") (pin "1") (pinfunction "NC_1") (pintype "bidirectional"))
    )
    (net (code "53") (name "unconnected-(J701-RSV-Pad8)") (class "Default")
      (node (ref "J701") (pin "8") (pinfunction "RSV_8") (pintype "bidirectional"))
    )
    (net (code "54") (name "unconnected-(U401-(AD0.1{slash}CAP0.2{slash}MAT0.2)P0.28-Pad13)") (class "Default")
      (node (ref "U401") (pin "13") (pinfunction "(AD0.1/CAP0.2/MAT0.2)P0.28_13") (pintype "bidirectional"))
    )
    (net (code "55") (name "unconnected-(U401-(AD0.2{slash}CAP0.3{slash}MAT0.3)P0.29-Pad14)") (class "Default")
      (node (ref "U401") (pin "14") (pinfunction "(AD0.2/CAP0.3/MAT0.3)P0.29_14") (pintype "bidirectional"))
    )
    (net (code "56") (name "unconnected-(U401-(AD0.3{slash}EINT3{slash}CAP0.0)P0.30-Pad15)") (class "Default")
      (node (ref "U401") (pin "15") (pinfunction "(AD0.3/EINT3/CAP0.0)P0.30_15") (pintype "bidirectional"))
    )
    (net (code "57") (name "unconnected-(U401-(AD0.4{slash}AOUT)P0.25-Pad9)") (class "Default")
      (node (ref "U401") (pin "9") (pinfunction "(AD0.4/AOUT)P0.25_9") (pintype "bidirectional"))
    )
    (net (code "58") (name "unconnected-(U401-(AD1.7{slash}CAP0.0{slash}MAT0.0)P0.22-Pad2)") (class "Default")
      (node (ref "U401") (pin "2") (pinfunction "(AD1.7/CAP0.0/MAT0.0)P0.22_2") (pintype "bidirectional"))
    )
    (net (code "59") (name "unconnected-(U401-(CAP1.3{slash}MISO1{slash}MAT1.3)P0.18-Pad53)") (class "Default")
      (node (ref "U401") (pin "53") (pinfunction "(CAP1.3/MISO1/MAT1.3)P0.18_53") (pintype "bidirectional"))
    )
    (net (code "60") (name "unconnected-(U401-(CTS1{slash}CAP1.1{slash}SCL1)P0.11-Pad37)") (class "Default")
      (node (ref "U401") (pin "37") (pinfunction "(CTS1/CAP1.1/SCL1)P0.11_37") (pintype "bidirectional"))
    )
    (net (code "61") (name "unconnected-(U401-(DSR1{slash}MAT1.0{slash}AD1.3)P0.12-Pad38)") (class "Default")
      (node (ref "U401") (pin "38") (pinfunction "(DSR1/MAT1.0/AD1.3)P0.12_38") (pintype "bidirectional"))
    )
    (net (code "62") (name "unconnected-(U401-(DTR1{slash}MAT1.1{slash}AD1.4)P0.13-Pad39)") (class "Default")
      (node (ref "U401") (pin "39") (pinfunction "(DTR1/MAT1.1/AD1.4)P0.13_39") (pintype "bidirectional"))
    )
    (net (code "63") (name "unconnected-(U401-(EINT0{slash}MAT0.2{slash}CAP0.2)P0.16-Pad46)") (class "Default")
      (node (ref "U401") (pin "46") (pinfunction "(EINT0/MAT0.2/CAP0.2)P0.16_46") (pintype "bidirectional"))
    )
    (net (code "64") (name "unconnected-(U401-(MAT1.2{slash}MOSI1{slash}CAP1.2)P0.19-Pad54)") (class "Default")
      (node (ref "U401") (pin "54") (pinfunction "(MAT1.2/MOSI1/CAP1.2)P0.19_54") (pintype "bidirectional"))
    )
    (net (code "65") (name "unconnected-(U401-(MAT1.3{slash}SSEL1{slash}EINT3)P0.20-Pad55)") (class "Default")
      (node (ref "U401") (pin "55") (pinfunction "(MAT1.3/SSEL1/EINT3)P0.20_55") (pintype "bidirectional"))
    )
    (net (code "66") (name "unconnected-(U401-(PWM5{slash}AD1.6{slash}CAP1.3)P0.21-Pad1)") (class "Default")
      (node (ref "U401") (pin "1") (pinfunction "(PWM5/AD1.6/CAP1.3)P0.21_1") (pintype "bidirectional"))
    )
    (net (code "67") (name "unconnected-(U401-P1.16(TRACEPKT0)-Pad16)") (class "Default")
      (node (ref "U401") (pin "16") (pinfunction "P1.16(TRACEPKT0)_16") (pintype "bidirectional"))
    )
    (net (code "68") (name "unconnected-(U401-P1.17(TRACEPKT1)-Pad12)") (class "Default")
      (node (ref "U401") (pin "12") (pinfunction "P1.17(TRACEPKT1)_12") (pintype "bidirectional"))
    )
    (net (code "69") (name "unconnected-(U401-P1.18(TRACEPKT2)-Pad8)") (class "Default")
      (node (ref "U401") (pin "8") (pinfunction "P1.18(TRACEPKT2)_8") (pintype "bidirectional"))
    )
    (net (code "70") (name "unconnected-(U401-P1.19(TRACEPKT3)-Pad4)") (class "Default")
      (node (ref "U401") (pin "4") (pinfunction "P1.19(TRACEPKT3)_4") (pintype "bidirectional"))
    )
    (net (code "71") (name "unconnected-(U401-P1.20(TRACESYNC)-Pad48)") (class "Default")
      (node (ref "U401") (pin "48") (pinfunction "P1.20(TRACESYNC)_48") (pintype "bidirectional"))
    )
    (net (code "72") (name "unconnected-(U401-P1.21(PIPESTAT0)-Pad44)") (class "Default")
      (node (ref "U401") (pin "44") (pinfunction "P1.21(PIPESTAT0)_44") (pintype "bidirectional"))
    )
    (net (code "73") (name "unconnected-(U401-P1.22(PIPESTAT1)-Pad40)") (class "Default")
      (node (ref "U401") (pin "40") (pinfunction "P1.22(PIPESTAT1)_40") (pintype "bidirectional"))
    )
    (net (code "74") (name "unconnected-(U401-P1.23(PIPESTAT2)-Pad36)") (class "Default")
      (node (ref "U401") (pin "36") (pinfunction "P1.23(PIPESTAT2)_36") (pintype "bidirectional"))
    )
    (net (code "75") (name "unconnected-(U401-P1.24(TRACECLK)-Pad32)") (class "Default")
      (node (ref "U401") (pin "32") (pinfunction "P1.24(TRACECLK)_32") (pintype "bidirectional"))
    )
    (net (code "76") (name "unconnected-(U401-P1.25(EXTIN0)-Pad28)") (class "Default")
      (node (ref "U401") (pin "28") (pinfunction "P1.25(EXTIN0)_28") (pintype "bidirectional"))
    )
    (net (code "77") (name "unconnected-(U401-P1.26(RTCK)-Pad24)") (class "Default")
      (node (ref "U401") (pin "24") (pinfunction "P1.26(RTCK)_24") (pintype "bidirectional"))
    )
    (net (code "78") (name "unconnected-(U401-P1.27(TDO)-Pad64)") (class "Default")
      (node (ref "U401") (pin "64") (pinfunction "P1.27(TDO)_64") (pintype "bidirectional"))
    )
    (net (code "79") (name "unconnected-(U401-P1.28(TDI)-Pad60)") (class "Default")
      (node (ref "U401") (pin "60") (pinfunction "P1.28(TDI)_60") (pintype "bidirectional"))
    )
    (net (code "80") (name "unconnected-(U401-P1.29(TCK)-Pad56)") (class "Default")
      (node (ref "U401") (pin "56") (pinfunction "P1.29(TCK)_56") (pintype "bidirectional"))
    )
    (net (code "81") (name "unconnected-(U401-P1.30(TMS)-Pad52)") (class "Default")
      (node (ref "U401") (pin "52") (pinfunction "P1.30(TMS)_52") (pintype "bidirectional"))
    )
    (net (code "82") (name "unconnected-(U401-P1.31({slash}TRST)-Pad20)") (class "Default")
      (node (ref "U401") (pin "20") (pinfunction "P1.31(/TRST)_20") (pintype "bidirectional"))
    )
    (net (code "83") (name "unconnected-(U601-CLKOUT-Pad22)") (class "Default")
      (node (ref "U601") (pin "22") (pinfunction "CLKOUT_22") (pintype "bidirectional"))
    )
    (net (code "84") (name "unconnected-(U601-ES_CL-Pad7)") (class "Default")
      (node (ref "U601") (pin "7") (pinfunction "ES_CL_7") (pintype "bidirectional"))
    )
    (net (code "85") (name "unconnected-(U601-ES_DA-Pad6)") (class "Default")
      (node (ref "U601") (pin "6") (pinfunction "ES_DA_6") (pintype "bidirectional"))
    )
    (net (code "86") (name "unconnected-(U801-NC-Pad3)") (class "Default")
      (node (ref "U801") (pin "3") (pinfunction "NC_3") (pintype "bidirectional"))
    )
    (net (code "87") (name "unconnected-(U801-NC-Pad5)") (class "Default")
      (node (ref "U801") (pin "5") (pinfunction "NC_5") (pintype "bidirectional"))
    )
    (net (code "88") (name "unconnected-(U801-NC-Pad6)") (class "Default")
      (node (ref "U801") (pin "6") (pinfunction "NC_6") (pintype "bidirectional"))
    )
    (net (code "89") (name "unconnected-(U801-NC-Pad7)") (class "Default")
      (node (ref "U801") (pin "7") (pinfunction "NC_7") (pintype "bidirectional"))
    )
    (net (code "90") (name "unconnected-(U801-NC-Pad14)") (class "Default")
      (node (ref "U801") (pin "14") (pinfunction "NC_14") (pintype "bidirectional"))
    )
  )
)
